# PrototypeV2.net
KiCad netlist of a schematic drawn in Altium Designer
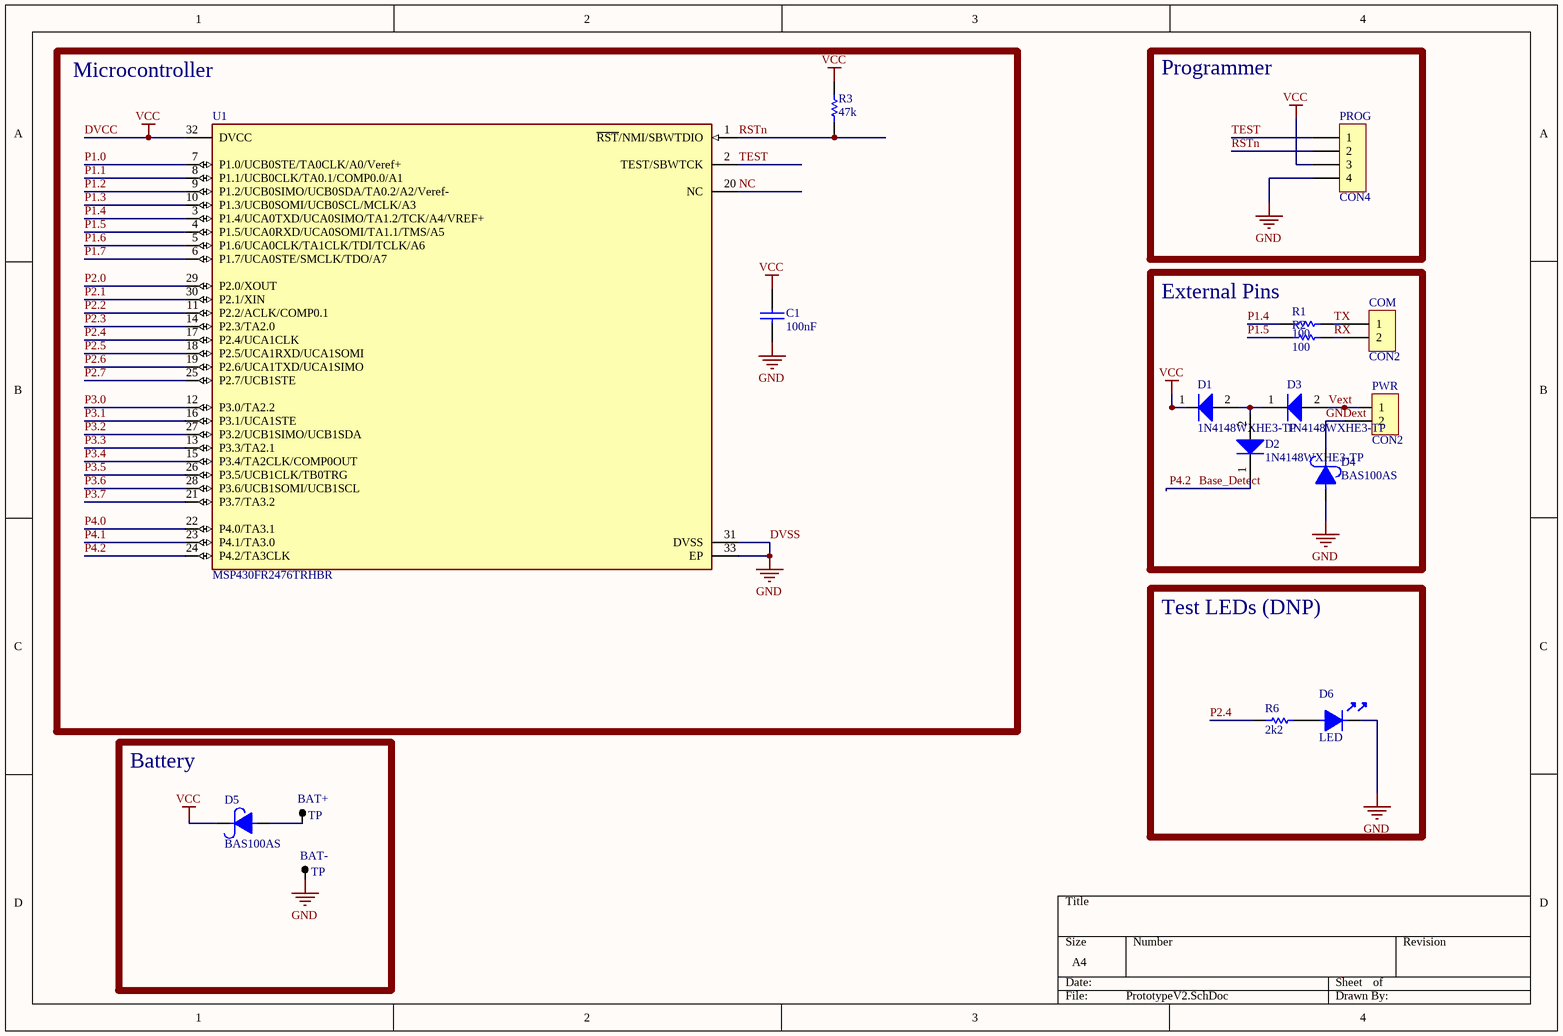
[diagram p0: PrototypeV2.SchDoc]

(export (version "E")
  (design (tool "Eeschema 10.0.6"))
  (components
    (comp (ref "BAT+") (value "TP") (footprint "TPTH") (libsource (lib "LIBEBAL") (part "TP")))
    (comp (ref "BAT-") (value "TP") (footprint "TPTH") (libsource (lib "LIBEBAL") (part "TP")))
    (comp (ref "C1") (value "100nF") (footprint "0805") (libsource (lib "LIBEBAL") (part "CAP")))
    (comp (ref "COM") (value "CON2") (footprint "SIP2") (libsource (lib "LIBEBAL") (part "CON2")))
    (comp (ref "D1")
      (value "1N4148WXHE3-TP")
      (footprint "ONSC-SOD-123-2-425-04_V")
      (description "Switching Diode, 2-Pin SOD-123, Pb-Free, Tape and Reel")
      (fields (field (name "PARTNUMBER") "MMSD4148T1G") (field (name "MANUFACTURER") "On Semiconductor"))
      (libsource (lib "Altium Content Vault") (part "ONSC-D-K1A2-2"))
    )
    (comp (ref "D2")
      (value "1N4148WXHE3-TP")
      (footprint "ONSC-SOD-123-2-425-04_V")
      (description "Switching Diode, 2-Pin SOD-123, Pb-Free, Tape and Reel")
      (fields (field (name "PARTNUMBER") "MMSD4148T1G") (field (name "MANUFACTURER") "On Semiconductor"))
      (libsource (lib "Altium Content Vault") (part "ONSC-D-K1A2-2"))
    )
    (comp (ref "D3")
      (value "1N4148WXHE3-TP")
      (footprint "ONSC-SOD-123-2-425-04_V")
      (description "Switching Diode, 2-Pin SOD-123, Pb-Free, Tape and Reel")
      (fields (field (name "PARTNUMBER") "MMSD4148T1G") (field (name "MANUFACTURER") "On Semiconductor"))
      (libsource (lib "Altium Content Vault") (part "ONSC-D-K1A2-2"))
    )
    (comp (ref "D4")
      (value "BAS100AS")
      (footprint "SODFL350X110-2N")
      (libsource (lib "LIBEBAL") (part "DIODO SCHOTTKY"))
    )
    (comp (ref "D5")
      (value "BAS100AS")
      (footprint "SODFL350X110-2N")
      (libsource (lib "LIBEBAL") (part "DIODO SCHOTTKY"))
    )
    (comp (ref "D6") (value "LED") (footprint "0805") (libsource (lib "LIBEBAL Tobi") (part "LED")))
    (comp (ref "PROG") (value "CON4") (footprint "SIP4") (libsource (lib "LIBEBAL") (part "CON4")))
    (comp (ref "PWR") (value "CON2") (footprint "SIP2") (libsource (lib "LIBEBAL") (part "CON2")))
    (comp (ref "R1") (value "100") (footprint "0805") (libsource (lib "LIBEBAL") (part "RES")))
    (comp (ref "R2") (value "100") (footprint "0805") (libsource (lib "LIBEBAL") (part "RES")))
    (comp (ref "R3") (value "47k") (footprint "0805") (libsource (lib "LIBEBAL") (part "RES")))
    (comp (ref "R6") (value "2k2") (footprint "0805") (libsource (lib "LIBEBAL") (part "RES")))
    (comp (ref "U1")
      (value "MSP430FR2476TRHBR")
      (footprint "FP-RHB0032E-IPC_A")
      (description "IC MCU 16BIT 64.5KB FRAM 32VQFN")
      (libsource (lib "Altium Content Vault") (part "0d2dbf59e938affcfd15988a6e728c5"))
    )
  )
  (nets
    (net (code "1") (name "/Base_Detect") (class "Default")
      (node (ref "D2") (pin "1") (pinfunction "K_1") (pintype "passive"))
      (node (ref "U1") (pin "24") (pinfunction "P4.2/TA3CLK_24") (pintype "bidirectional"))
    )
    (net (code "2") (name "/GNDext") (class "Default")
      (node (ref "D4") (pin "2") (pinfunction "2_2") (pintype "passive"))
      (node (ref "PWR") (pin "2") (pinfunction "2_2") (pintype "passive"))
    )
    (net (code "3") (name "/NC") (class "Default")
      (node (ref "U1") (pin "20") (pinfunction "NC_20") (pintype "passive"))
    )
    (net (code "4") (name "/P1.0") (class "Default")
      (node (ref "U1") (pin "7") (pinfunction "P1.0/UCB0STE/TA0CLK/A0/Veref+_7") (pintype "bidirectional"))
    )
    (net (code "5") (name "/P1.1") (class "Default")
      (node (ref "U1") (pin "8") (pinfunction "P1.1/UCB0CLK/TA0.1/COMP0.0/A1_8") (pintype "bidirectional"))
    )
    (net (code "6") (name "/P1.2") (class "Default")
      (node (ref "U1") (pin "9") (pinfunction "P1.2/UCB0SIMO/UCB0SDA/TA0.2/A2/Veref-_9") (pintype "bidirectional"))
    )
    (net (code "7") (name "/P1.3") (class "Default")
      (node (ref "U1") (pin "10") (pinfunction "P1.3/UCB0SOMI/UCB0SCL/MCLK/A3_10") (pintype "bidirectional"))
    )
    (net (code "8") (name "/P1.4") (class "Default")
      (node (ref "R1") (pin "1") (pinfunction "1_1") (pintype "passive"))
      (node (ref "U1") (pin "3") (pinfunction "P1.4/UCA0TXD/UCA0SIMO/TA1.2/TCK/A4/VREF+_3") (pintype "bidirectional"))
    )
    (net (code "9") (name "/P1.5") (class "Default")
      (node (ref "R2") (pin "2") (pinfunction "2_2") (pintype "passive"))
      (node (ref "U1") (pin "4") (pinfunction "P1.5/UCA0RXD/UCA0SOMI/TA1.1/TMS/A5_4") (pintype "bidirectional"))
    )
    (net (code "10") (name "/P1.6") (class "Default")
      (node (ref "U1") (pin "5") (pinfunction "P1.6/UCA0CLK/TA1CLK/TDI/TCLK/A6_5") (pintype "bidirectional"))
    )
    (net (code "11") (name "/P1.7") (class "Default")
      (node (ref "U1") (pin "6") (pinfunction "P1.7/UCA0STE/SMCLK/TDO/A7_6") (pintype "bidirectional"))
    )
    (net (code "12") (name "/P2.0") (class "Default")
      (node (ref "U1") (pin "29") (pinfunction "P2.0/XOUT_29") (pintype "bidirectional"))
    )
    (net (code "13") (name "/P2.1") (class "Default")
      (node (ref "U1") (pin "30") (pinfunction "P2.1/XIN_30") (pintype "bidirectional"))
    )
    (net (code "14") (name "/P2.2") (class "Default")
      (node (ref "U1") (pin "11") (pinfunction "P2.2/ACLK/COMP0.1_11") (pintype "bidirectional"))
    )
    (net (code "15") (name "/P2.3") (class "Default")
      (node (ref "U1") (pin "14") (pinfunction "P2.3/TA2.0_14") (pintype "bidirectional"))
    )
    (net (code "16") (name "/P2.4") (class "Default")
      (node (ref "R6") (pin "2") (pinfunction "2_2") (pintype "passive"))
      (node (ref "U1") (pin "17") (pinfunction "P2.4/UCA1CLK_17") (pintype "bidirectional"))
    )
    (net (code "17") (name "/P2.5") (class "Default")
      (node (ref "U1") (pin "18") (pinfunction "P2.5/UCA1RXD/UCA1SOMI_18") (pintype "bidirectional"))
    )
    (net (code "18") (name "/P2.6") (class "Default")
      (node (ref "U1") (pin "19") (pinfunction "P2.6/UCA1TXD/UCA1SIMO_19") (pintype "bidirectional"))
    )
    (net (code "19") (name "/P2.7") (class "Default")
      (node (ref "U1") (pin "25") (pinfunction "P2.7/UCB1STE_25") (pintype "bidirectional"))
    )
    (net (code "20") (name "/P3.0") (class "Default")
      (node (ref "U1") (pin "12") (pinfunction "P3.0/TA2.2_12") (pintype "bidirectional"))
    )
    (net (code "21") (name "/P3.1") (class "Default")
      (node (ref "U1") (pin "16") (pinfunction "P3.1/UCA1STE_16") (pintype "bidirectional"))
    )
    (net (code "22") (name "/P3.2") (class "Default")
      (node (ref "U1") (pin "27") (pinfunction "P3.2/UCB1SIMO/UCB1SDA_27") (pintype "bidirectional"))
    )
    (net (code "23") (name "/P3.3") (class "Default")
      (node (ref "U1") (pin "13") (pinfunction "P3.3/TA2.1_13") (pintype "bidirectional"))
    )
    (net (code "24") (name "/P3.4") (class "Default")
      (node (ref "U1") (pin "15") (pinfunction "P3.4/TA2CLK/COMP0OUT_15") (pintype "bidirectional"))
    )
    (net (code "25") (name "/P3.5") (class "Default")
      (node (ref "U1") (pin "26") (pinfunction "P3.5/UCB1CLK/TB0TRG_26") (pintype "bidirectional"))
    )
    (net (code "26") (name "/P3.6") (class "Default")
      (node (ref "U1") (pin "28") (pinfunction "P3.6/UCB1SOMI/UCB1SCL_28") (pintype "bidirectional"))
    )
    (net (code "27") (name "/P3.7") (class "Default")
      (node (ref "U1") (pin "21") (pinfunction "P3.7/TA3.2_21") (pintype "bidirectional"))
    )
    (net (code "28") (name "/P4.0") (class "Default")
      (node (ref "U1") (pin "22") (pinfunction "P4.0/TA3.1_22") (pintype "bidirectional"))
    )
    (net (code "29") (name "/P4.1") (class "Default")
      (node (ref "U1") (pin "23") (pinfunction "P4.1/TA3.0_23") (pintype "bidirectional"))
    )
    (net (code "30") (name "/RSTn") (class "Default")
      (node (ref "PROG") (pin "2") (pinfunction "2_2") (pintype "passive"))
      (node (ref "R3") (pin "2") (pinfunction "2_2") (pintype "passive"))
      (node (ref "U1") (pin "1") (pinfunction "~{RST}/NMI/SBWTDIO_1") (pintype "input"))
    )
    (net (code "31") (name "/RX") (class "Default")
      (node (ref "COM") (pin "2") (pinfunction "2_2") (pintype "passive"))
      (node (ref "R2") (pin "1") (pinfunction "1_1") (pintype "passive"))
    )
    (net (code "32") (name "/TEST") (class "Default")
      (node (ref "PROG") (pin "1") (pinfunction "1_1") (pintype "passive"))
      (node (ref "U1") (pin "2") (pinfunction "TEST/SBWTCK_2") (pintype "passive"))
    )
    (net (code "33") (name "/TX") (class "Default")
      (node (ref "COM") (pin "1") (pinfunction "1_1") (pintype "passive"))
      (node (ref "R1") (pin "2") (pinfunction "2_2") (pintype "passive"))
    )
    (net (code "34") (name "/Vext") (class "Default")
      (node (ref "D3") (pin "2") (pinfunction "A_2") (pintype "passive"))
      (node (ref "PWR") (pin "1") (pinfunction "1_1") (pintype "passive"))
    )
    (net (code "35") (name "GND") (class "Default")
      (node (ref "BAT-") (pin "1") (pinfunction "1_1") (pintype "passive"))
      (node (ref "C1") (pin "2") (pinfunction "2_2") (pintype "passive"))
      (node (ref "D4") (pin "1") (pinfunction "1_1") (pintype "passive"))
      (node (ref "D6") (pin "2") (pinfunction "2_2") (pintype "passive"))
      (node (ref "PROG") (pin "4") (pinfunction "4_4") (pintype "passive"))
      (node (ref "U1") (pin "31") (pinfunction "DVSS_31") (pintype "power_in"))
      (node (ref "U1") (pin "33") (pinfunction "EP_33") (pintype "power_in"))
    )
    (net (code "36") (name "Net-(BAT+-Pad1)") (class "Default")
      (node (ref "BAT+") (pin "1") (pinfunction "1_1") (pintype "passive"))
      (node (ref "D5") (pin "1") (pinfunction "1_1") (pintype "passive"))
    )
    (net (code "37") (name "Net-(D1-A)") (class "Default")
      (node (ref "D1") (pin "2") (pinfunction "A_2") (pintype "passive"))
      (node (ref "D2") (pin "2") (pinfunction "A_2") (pintype "passive"))
      (node (ref "D3") (pin "1") (pinfunction "K_1") (pintype "passive"))
    )
    (net (code "38") (name "Net-(D6-Pad1)") (class "Default")
      (node (ref "D6") (pin "1") (pinfunction "1_1") (pintype "passive"))
      (node (ref "R6") (pin "1") (pinfunction "1_1") (pintype "passive"))
    )
    (net (code "39") (name "VCC") (class "Default")
      (node (ref "C1") (pin "1") (pinfunction "1_1") (pintype "passive"))
      (node (ref "D1") (pin "1") (pinfunction "K_1") (pintype "passive"))
      (node (ref "D5") (pin "2") (pinfunction "2_2") (pintype "passive"))
      (node (ref "PROG") (pin "3") (pinfunction "3_3") (pintype "passive"))
      (node (ref "R3") (pin "1") (pinfunction "1_1") (pintype "passive"))
      (node (ref "U1") (pin "32") (pinfunction "DVCC_32") (pintype "power_in"))
    )
  )
)
